# PRSC-2101-THCFS-1V3_eagle7.net
KiCad netlist of a schematic drawn in EAGLE
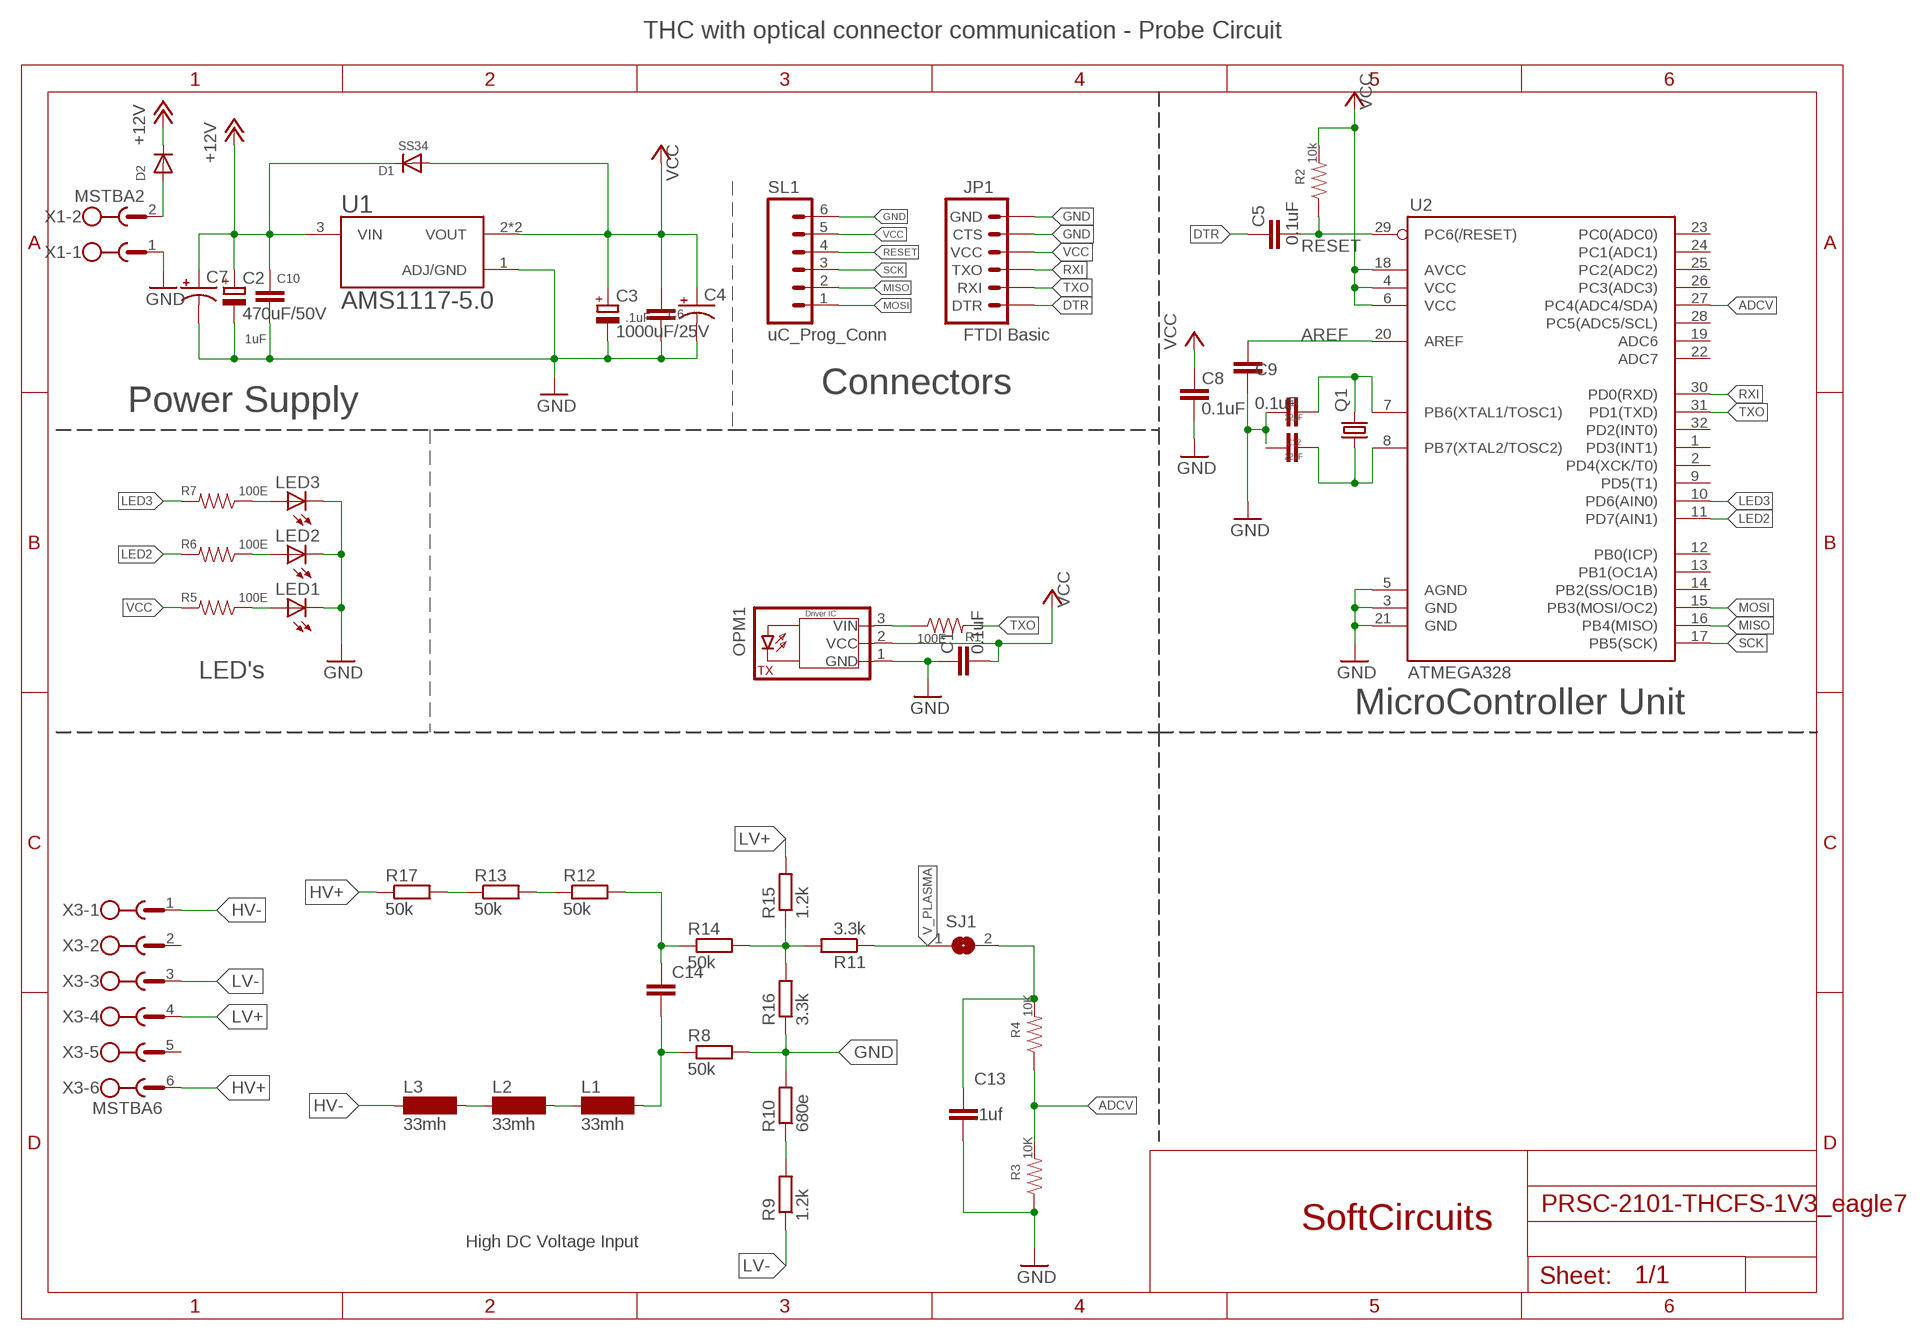
[diagram p0: schematic, sheet 1]

(export (version "E")
  (design (tool "Eeschema 10.0.6"))
  (components
    (comp (ref "C1")
      (value "0.1uF")
      (footprint "eagle-import:C1206")
      (libsource (lib "eagle-import") (part "C-EUC1206"))
    )
    (comp (ref "C2")
      (value "470uF/50V")
      (footprint "eagle-import:153CLV-1010")
      (libsource (lib "eagle-import") (part "CPOL-EU153CLV-1010"))
    )
    (comp (ref "C3")
      (value "1000uF/25V")
      (footprint "eagle-import:153CLV-1010")
      (libsource (lib "eagle-import") (part "CPOL-EU153CLV-1010"))
    )
    (comp (ref "C4")
      (value "CAP_POL3528-KIT")
      (footprint "eagle-import:EIA3528-KIT")
      (libsource (lib "eagle-import") (part "CAP_POL3528-KIT"))
    )
    (comp (ref "C5")
      (value "0.1uF")
      (footprint "eagle-import:C1206")
      (libsource (lib "eagle-import") (part "C-EUC1206"))
    )
    (comp (ref "C6")
      (value ".1uF")
      (footprint "eagle-import:C1206")
      (libsource (lib "eagle-import") (part "C-EUC1206"))
    )
    (comp (ref "C7")
      (value "CAP_POL3528-KIT")
      (footprint "eagle-import:EIA3528-KIT")
      (libsource (lib "eagle-import") (part "CAP_POL3528-KIT"))
    )
    (comp (ref "C8")
      (value "0.1uF")
      (footprint "eagle-import:C1206")
      (libsource (lib "eagle-import") (part "C-EUC1206"))
    )
    (comp (ref "C9")
      (value "0.1uF")
      (footprint "eagle-import:C1206")
      (libsource (lib "eagle-import") (part "C-EUC1206"))
    )
    (comp (ref "C10")
      (value "1uF")
      (footprint "eagle-import:C1206")
      (libsource (lib "eagle-import") (part "C-EUC1206"))
    )
    (comp (ref "C11")
      (value "22pF")
      (footprint "eagle-import:C1206")
      (libsource (lib "eagle-import") (part "C-EUC1206"))
    )
    (comp (ref "C12")
      (value "22pF")
      (footprint "eagle-import:C1206")
      (libsource (lib "eagle-import") (part "C-EUC1206"))
    )
    (comp (ref "C13")
      (value ".1uf")
      (footprint "eagle-import:C1206")
      (libsource (lib "eagle-import") (part "C-EUC1206"))
    )
    (comp (ref "C14")
      (value "C-EU050-025X075")
      (footprint "eagle-import:C050-025X075")
      (libsource (lib "eagle-import") (part "rcl_C-EU050-025X075"))
    )
    (comp (ref "D1")
      (value "SS34")
      (footprint "eagle-import:SMADIODE")
      (libsource (lib "eagle-import") (part "DIODESMA"))
    )
    (comp (ref "D2")
      (value "DIODESMA")
      (footprint "eagle-import:SMADIODE")
      (libsource (lib "eagle-import") (part "DIODESMA"))
    )
    (comp (ref "JP1")
      (value "FTDI Basic")
      (footprint "eagle-import:1X06")
      (libsource (lib "eagle-import") (part "ARDUINO_SERIAL_PROGRAMPTH"))
    )
    (comp (ref "L1")
      (value "33mh")
      (footprint "eagle-import:MY_INDUCTOR")
      (libsource (lib "eagle-import") (part "SD12"))
    )
    (comp (ref "L2")
      (value "33mh")
      (footprint "eagle-import:MY_INDUCTOR")
      (libsource (lib "eagle-import") (part "SD12"))
    )
    (comp (ref "L3")
      (value "33mh")
      (footprint "eagle-import:MY_INDUCTOR")
      (libsource (lib "eagle-import") (part "SD12"))
    )
    (comp (ref "LED1")
      (value "LED3MM")
      (footprint "eagle-import:LED3MM")
      (libsource (lib "eagle-import") (part "LED3MM"))
    )
    (comp (ref "LED2")
      (value "LED3MM")
      (footprint "eagle-import:LED3MM")
      (libsource (lib "eagle-import") (part "LED3MM"))
    )
    (comp (ref "LED3")
      (value "LED3MM")
      (footprint "eagle-import:LED3MM")
      (libsource (lib "eagle-import") (part "LED3MM"))
    )
    (comp (ref "OPM1")
      (value "TOSLINK_DQT-025")
      (footprint "eagle-import:TOSLINK_DQ-025")
      (libsource (lib "eagle-import") (part "TOSLINK_DQT-025"))
    )
    (comp (ref "Q1")
      (value "CRYSTALHC49UP")
      (footprint "eagle-import:HC49UP")
      (libsource (lib "eagle-import") (part "CRYSTALHC49UP"))
    )
    (comp (ref "R1")
      (value "100E")
      (footprint "eagle-import:1206")
      (libsource (lib "eagle-import") (part "RESISTOR1206"))
    )
    (comp (ref "R2")
      (value "10k")
      (footprint "eagle-import:1206")
      (libsource (lib "eagle-import") (part "RESISTOR1206"))
    )
    (comp (ref "R3")
      (value "10K")
      (footprint "eagle-import:1206")
      (libsource (lib "eagle-import") (part "RESISTOR1206"))
    )
    (comp (ref "R4")
      (value "10K")
      (footprint "eagle-import:1206")
      (libsource (lib "eagle-import") (part "RESISTOR1206"))
    )
    (comp (ref "R5")
      (value "100E")
      (footprint "eagle-import:1206")
      (libsource (lib "eagle-import") (part "RESISTOR1206"))
    )
    (comp (ref "R6")
      (value "100E")
      (footprint "eagle-import:1206")
      (libsource (lib "eagle-import") (part "RESISTOR1206"))
    )
    (comp (ref "R7")
      (value "100E")
      (footprint "eagle-import:1206")
      (libsource (lib "eagle-import") (part "RESISTOR1206"))
    )
    (comp (ref "R8")
      (value "50k")
      (footprint "eagle-import:0207_5V")
      (libsource (lib "eagle-import") (part "R-EU_0207/5V"))
    )
    (comp (ref "R9")
      (value "1.2k")
      (footprint "eagle-import:0207_2V")
      (libsource (lib "eagle-import") (part "R-EU_0207/2V"))
    )
    (comp (ref "R10")
      (value "680e")
      (footprint "eagle-import:0207_5V")
      (libsource (lib "eagle-import") (part "R-EU_0207/5V"))
    )
    (comp (ref "R11")
      (value "3.3k")
      (footprint "eagle-import:0207_2V")
      (libsource (lib "eagle-import") (part "R-EU_0207/2V"))
    )
    (comp (ref "R12")
      (value "50k")
      (footprint "eagle-import:0207_5V")
      (libsource (lib "eagle-import") (part "R-EU_0207/5V"))
    )
    (comp (ref "R13")
      (value "50k")
      (footprint "eagle-import:0207_5V")
      (libsource (lib "eagle-import") (part "R-EU_0207/5V"))
    )
    (comp (ref "R14")
      (value "50k")
      (footprint "eagle-import:0207_5V")
      (libsource (lib "eagle-import") (part "R-EU_0207/5V"))
    )
    (comp (ref "R15")
      (value "1.2k")
      (footprint "eagle-import:0207_2V")
      (libsource (lib "eagle-import") (part "R-EU_0207/2V"))
    )
    (comp (ref "R16")
      (value "3.3k")
      (footprint "eagle-import:0207_15")
      (libsource (lib "eagle-import") (part "R-EU_0207/15"))
    )
    (comp (ref "R17")
      (value "50k")
      (footprint "eagle-import:0207_5V")
      (libsource (lib "eagle-import") (part "R-EU_0207/5V"))
    )
    (comp (ref "SJ1") (value "SJ") (footprint "eagle-import:SJ") (libsource (lib "eagle-import") (part "SJ")))
    (comp (ref "SL1")
      (value "uC_Prog_Conn")
      (footprint "eagle-import:06P")
      (libsource (lib "eagle-import") (part "M06"))
    )
    (comp (ref "U1")
      (value "AMS1117-5.0")
      (footprint "eagle-import:SOT229P700X180-4N")
      (fields (field (name "MF") "Advanced Monolithic Systems"))
      (libsource (lib "eagle-import") (part "AMS1117-5.0"))
    )
    (comp (ref "U2")
      (value "ATMEGA328")
      (footprint "eagle-import:TQFP32-08")
      (libsource (lib "eagle-import") (part "ATMEGA168"))
    )
    (comp (ref "X1")
      (value "MSTBA2")
      (footprint "eagle-import:MSTBA2")
      (fields (field (name "MF") "FARNELL") (field (name "MPN") "1757242"))
      (libsource (lib "eagle-import") (part "MSTBA2"))
    )
    (comp (ref "X3")
      (value "MSTBA6")
      (footprint "eagle-import:MSTBA6")
      (fields (field (name "MF") "FARNELL") (field (name "MPN") "1757284"))
      (libsource (lib "eagle-import") (part "MSTBA6"))
    )
  )
  (nets
    (net (code "1") (name "+12V") (class "Default")
      (node (ref "C10") (pin "1") (pinfunction "1_1") (pintype "passive"))
      (node (ref "C2") (pin "+") (pinfunction "+_+") (pintype "passive"))
      (node (ref "C7") (pin "A") (pinfunction "+_A") (pintype "passive"))
      (node (ref "D1") (pin "C") (pinfunction "C_C") (pintype "passive"))
      (node (ref "D2") (pin "C") (pinfunction "C_C") (pintype "passive"))
      (node (ref "U1") (pin "3") (pinfunction "VIN_3") (pintype "input"))
    )
    (net (code "2") (name "/AREF") (class "Default")
      (node (ref "C9") (pin "2") (pinfunction "2_2") (pintype "passive"))
      (node (ref "U2") (pin "20") (pinfunction "AREF_20") (pintype "bidirectional"))
    )
    (net (code "3") (name "ADCV") (class "Default")
      (node (ref "R3") (pin "2") (pinfunction "2_2") (pintype "passive"))
      (node (ref "R4") (pin "1") (pinfunction "1_1") (pintype "passive"))
      (node (ref "U2") (pin "27") (pinfunction "PC4(ADC4/SDA)_27") (pintype "bidirectional"))
    )
    (net (code "4") (name "DTR") (class "Default")
      (node (ref "C5") (pin "2") (pinfunction "2_2") (pintype "passive"))
      (node (ref "JP1") (pin "1") (pinfunction "DTR_1") (pintype "passive"))
    )
    (net (code "5") (name "GND") (class "Default")
      (node (ref "C1") (pin "2") (pinfunction "2_2") (pintype "passive"))
      (node (ref "C10") (pin "2") (pinfunction "2_2") (pintype "passive"))
      (node (ref "C11") (pin "2") (pinfunction "2_2") (pintype "passive"))
      (node (ref "C12") (pin "2") (pinfunction "2_2") (pintype "passive"))
      (node (ref "C13") (pin "2") (pinfunction "2_2") (pintype "passive"))
      (node (ref "C2") (pin "-") (pinfunction "-_-") (pintype "passive"))
      (node (ref "C3") (pin "-") (pinfunction "-_-") (pintype "passive"))
      (node (ref "C4") (pin "C") (pinfunction "-_C") (pintype "passive"))
      (node (ref "C6") (pin "2") (pinfunction "2_2") (pintype "passive"))
      (node (ref "C7") (pin "C") (pinfunction "-_C") (pintype "passive"))
      (node (ref "C8") (pin "1") (pinfunction "1_1") (pintype "passive"))
      (node (ref "C9") (pin "1") (pinfunction "1_1") (pintype "passive"))
      (node (ref "JP1") (pin "5") (pinfunction "CTS_5") (pintype "passive"))
      (node (ref "JP1") (pin "6") (pinfunction "GND_6") (pintype "passive"))
      (node (ref "LED1") (pin "K") (pinfunction "C_K") (pintype "passive"))
      (node (ref "LED2") (pin "K") (pinfunction "C_K") (pintype "passive"))
      (node (ref "LED3") (pin "K") (pinfunction "C_K") (pintype "passive"))
      (node (ref "OPM1") (pin "1") (pinfunction "GND_1") (pintype "passive"))
      (node (ref "R10") (pin "2") (pinfunction "2_2") (pintype "passive"))
      (node (ref "R16") (pin "1") (pinfunction "1_1") (pintype "passive"))
      (node (ref "R3") (pin "1") (pinfunction "1_1") (pintype "passive"))
      (node (ref "R8") (pin "2") (pinfunction "2_2") (pintype "passive"))
      (node (ref "SL1") (pin "6") (pinfunction "6_6") (pintype "passive"))
      (node (ref "U1") (pin "1") (pinfunction "ADJ/GND_1") (pintype "power_in"))
      (node (ref "U2") (pin "21") (pinfunction "GND_21") (pintype "bidirectional"))
      (node (ref "U2") (pin "3") (pinfunction "GND_3") (pintype "bidirectional"))
      (node (ref "U2") (pin "5") (pinfunction "AGND_5") (pintype "bidirectional"))
      (node (ref "X1") (pin "1") (pinfunction "1_1") (pintype "passive"))
    )
    (net (code "6") (name "HV+") (class "Default")
      (node (ref "R17") (pin "1") (pinfunction "1_1") (pintype "passive"))
      (node (ref "X3") (pin "6") (pinfunction "1_6") (pintype "passive"))
    )
    (net (code "7") (name "HV-") (class "Default")
      (node (ref "L3") (pin "1") (pinfunction "1_1") (pintype "passive"))
      (node (ref "X3") (pin "1") (pinfunction "1_1") (pintype "passive"))
    )
    (net (code "8") (name "LED2") (class "Default")
      (node (ref "R6") (pin "2") (pinfunction "2_2") (pintype "passive"))
      (node (ref "U2") (pin "11") (pinfunction "PD7(AIN1)_11") (pintype "bidirectional"))
    )
    (net (code "9") (name "LED3") (class "Default")
      (node (ref "R7") (pin "2") (pinfunction "2_2") (pintype "passive"))
      (node (ref "U2") (pin "10") (pinfunction "PD6(AIN0)_10") (pintype "bidirectional"))
    )
    (net (code "10") (name "LV+") (class "Default")
      (node (ref "R15") (pin "2") (pinfunction "2_2") (pintype "passive"))
      (node (ref "X3") (pin "4") (pinfunction "1_4") (pintype "passive"))
    )
    (net (code "11") (name "LV-") (class "Default")
      (node (ref "R9") (pin "1") (pinfunction "1_1") (pintype "passive"))
      (node (ref "X3") (pin "3") (pinfunction "1_3") (pintype "passive"))
    )
    (net (code "12") (name "MISO") (class "Default")
      (node (ref "SL1") (pin "2") (pinfunction "2_2") (pintype "passive"))
      (node (ref "U2") (pin "16") (pinfunction "PB4(MISO)_16") (pintype "bidirectional"))
    )
    (net (code "13") (name "MOSI") (class "Default")
      (node (ref "SL1") (pin "1") (pinfunction "1_1") (pintype "passive"))
      (node (ref "U2") (pin "15") (pinfunction "PB3(MOSI/OC2)_15") (pintype "bidirectional"))
    )
    (net (code "14") (name "Net-(C13-Pad1)") (class "Default")
      (node (ref "C13") (pin "1") (pinfunction "1_1") (pintype "passive"))
      (node (ref "R4") (pin "2") (pinfunction "2_2") (pintype "passive"))
      (node (ref "SJ1") (pin "2") (pinfunction "2_2") (pintype "passive"))
    )
    (net (code "15") (name "Net-(C14-Pad1)") (class "Default")
      (node (ref "C14") (pin "1") (pinfunction "1_1") (pintype "passive"))
      (node (ref "R12") (pin "2") (pinfunction "2_2") (pintype "passive"))
      (node (ref "R14") (pin "1") (pinfunction "1_1") (pintype "passive"))
    )
    (net (code "16") (name "Net-(C14-Pad2)") (class "Default")
      (node (ref "C14") (pin "2") (pinfunction "2_2") (pintype "passive"))
      (node (ref "L1") (pin "2") (pinfunction "2_2") (pintype "passive"))
      (node (ref "R8") (pin "1") (pinfunction "1_1") (pintype "passive"))
    )
    (net (code "17") (name "Net-(L1-Pad1)") (class "Default")
      (node (ref "L1") (pin "1") (pinfunction "1_1") (pintype "passive"))
      (node (ref "L2") (pin "2") (pinfunction "2_2") (pintype "passive"))
    )
    (net (code "18") (name "Net-(L2-Pad1)") (class "Default")
      (node (ref "L2") (pin "1") (pinfunction "1_1") (pintype "passive"))
      (node (ref "L3") (pin "2") (pinfunction "2_2") (pintype "passive"))
    )
    (net (code "19") (name "Net-(LED1-PadA)") (class "Default")
      (node (ref "LED1") (pin "A") (pinfunction "A_A") (pintype "passive"))
      (node (ref "R5") (pin "1") (pinfunction "1_1") (pintype "passive"))
    )
    (net (code "20") (name "Net-(LED2-PadA)") (class "Default")
      (node (ref "LED2") (pin "A") (pinfunction "A_A") (pintype "passive"))
      (node (ref "R6") (pin "1") (pinfunction "1_1") (pintype "passive"))
    )
    (net (code "21") (name "Net-(LED3-PadA)") (class "Default")
      (node (ref "LED3") (pin "A") (pinfunction "A_A") (pintype "passive"))
      (node (ref "R7") (pin "1") (pinfunction "1_1") (pintype "passive"))
    )
    (net (code "22") (name "Net-(OPM1-VIN)") (class "Default")
      (node (ref "OPM1") (pin "3") (pinfunction "VIN_3") (pintype "passive"))
      (node (ref "R1") (pin "1") (pinfunction "1_1") (pintype "passive"))
    )
    (net (code "23") (name "Net-(R10-Pad1)") (class "Default")
      (node (ref "R10") (pin "1") (pinfunction "1_1") (pintype "passive"))
      (node (ref "R9") (pin "2") (pinfunction "2_2") (pintype "passive"))
    )
    (net (code "24") (name "Net-(R11-Pad2)") (class "Default")
      (node (ref "R11") (pin "2") (pinfunction "2_2") (pintype "passive"))
      (node (ref "R14") (pin "2") (pinfunction "2_2") (pintype "passive"))
      (node (ref "R15") (pin "1") (pinfunction "1_1") (pintype "passive"))
      (node (ref "R16") (pin "2") (pinfunction "2_2") (pintype "passive"))
    )
    (net (code "25") (name "Net-(R12-Pad1)") (class "Default")
      (node (ref "R12") (pin "1") (pinfunction "1_1") (pintype "passive"))
      (node (ref "R13") (pin "2") (pinfunction "2_2") (pintype "passive"))
    )
    (net (code "26") (name "Net-(R13-Pad1)") (class "Default")
      (node (ref "R13") (pin "1") (pinfunction "1_1") (pintype "passive"))
      (node (ref "R17") (pin "2") (pinfunction "2_2") (pintype "passive"))
    )
    (net (code "27") (name "Net-(U2-PB6(XTAL1{slash}TOSC1))") (class "Default")
      (node (ref "C11") (pin "1") (pinfunction "1_1") (pintype "passive"))
      (node (ref "Q1") (pin "2") (pinfunction "2_2") (pintype "passive"))
      (node (ref "U2") (pin "7") (pinfunction "PB6(XTAL1/TOSC1)_7") (pintype "bidirectional"))
    )
    (net (code "28") (name "Net-(U2-PB7(XTAL2{slash}TOSC2))") (class "Default")
      (node (ref "C12") (pin "1") (pinfunction "1_1") (pintype "passive"))
      (node (ref "Q1") (pin "1") (pinfunction "1_1") (pintype "passive"))
      (node (ref "U2") (pin "8") (pinfunction "PB7(XTAL2/TOSC2)_8") (pintype "bidirectional"))
    )
    (net (code "29") (name "Net-(X1B-1)") (class "Default")
      (node (ref "D2") (pin "A") (pinfunction "A_A") (pintype "passive"))
      (node (ref "X1") (pin "2") (pinfunction "1_2") (pintype "passive"))
    )
    (net (code "30") (name "RESET") (class "Default")
      (node (ref "C5") (pin "1") (pinfunction "1_1") (pintype "passive"))
      (node (ref "R2") (pin "1") (pinfunction "1_1") (pintype "passive"))
      (node (ref "SL1") (pin "4") (pinfunction "4_4") (pintype "passive"))
      (node (ref "U2") (pin "29") (pinfunction "PC6(/RESET)_29") (pintype "bidirectional"))
    )
    (net (code "31") (name "RXI") (class "Default")
      (node (ref "JP1") (pin "3") (pinfunction "TXO_3") (pintype "passive"))
      (node (ref "U2") (pin "30") (pinfunction "PD0(RXD)_30") (pintype "bidirectional"))
    )
    (net (code "32") (name "SCK") (class "Default")
      (node (ref "SL1") (pin "3") (pinfunction "3_3") (pintype "passive"))
      (node (ref "U2") (pin "17") (pinfunction "PB5(SCK)_17") (pintype "bidirectional"))
    )
    (net (code "33") (name "TXO") (class "Default")
      (node (ref "JP1") (pin "2") (pinfunction "RXI_2") (pintype "passive"))
      (node (ref "R1") (pin "2") (pinfunction "2_2") (pintype "passive"))
      (node (ref "U2") (pin "31") (pinfunction "PD1(TXD)_31") (pintype "bidirectional"))
    )
    (net (code "34") (name "VCC") (class "Default")
      (node (ref "C1") (pin "1") (pinfunction "1_1") (pintype "passive"))
      (node (ref "C3") (pin "+") (pinfunction "+_+") (pintype "passive"))
      (node (ref "C4") (pin "A") (pinfunction "+_A") (pintype "passive"))
      (node (ref "C6") (pin "1") (pinfunction "1_1") (pintype "passive"))
      (node (ref "C8") (pin "2") (pinfunction "2_2") (pintype "passive"))
      (node (ref "D1") (pin "A") (pinfunction "A_A") (pintype "passive"))
      (node (ref "JP1") (pin "4") (pinfunction "VCC_4") (pintype "passive"))
      (node (ref "OPM1") (pin "2") (pinfunction "VCC_2") (pintype "bidirectional"))
      (node (ref "R2") (pin "2") (pinfunction "2_2") (pintype "passive"))
      (node (ref "R5") (pin "2") (pinfunction "2_2") (pintype "passive"))
      (node (ref "SL1") (pin "5") (pinfunction "5_5") (pintype "passive"))
      (node (ref "U1") (pin "2") (pinfunction "VOUT_2") (pintype "output"))
      (node (ref "U1") (pin "4") (pinfunction "VOUT_4") (pintype "output"))
      (node (ref "U2") (pin "18") (pinfunction "AVCC_18") (pintype "bidirectional"))
      (node (ref "U2") (pin "4") (pinfunction "VCC_4") (pintype "bidirectional"))
      (node (ref "U2") (pin "6") (pinfunction "VCC_6") (pintype "bidirectional"))
    )
    (net (code "35") (name "V_PLASMA") (class "Default")
      (node (ref "R11") (pin "1") (pinfunction "1_1") (pintype "passive"))
      (node (ref "SJ1") (pin "1") (pinfunction "1_1") (pintype "passive"))
    )
    (net (code "36") (name "unconnected-(U2-ADC6-Pad19)") (class "Default")
      (node (ref "U2") (pin "19") (pinfunction "ADC6_19") (pintype "bidirectional"))
    )
    (net (code "37") (name "unconnected-(U2-ADC7-Pad22)") (class "Default")
      (node (ref "U2") (pin "22") (pinfunction "ADC7_22") (pintype "bidirectional"))
    )
    (net (code "38") (name "unconnected-(U2-PB0(ICP)-Pad12)") (class "Default")
      (node (ref "U2") (pin "12") (pinfunction "PB0(ICP)_12") (pintype "bidirectional"))
    )
    (net (code "39") (name "unconnected-(U2-PB1(OC1A)-Pad13)") (class "Default")
      (node (ref "U2") (pin "13") (pinfunction "PB1(OC1A)_13") (pintype "bidirectional"))
    )
    (net (code "40") (name "unconnected-(U2-PB2(SS{slash}OC1B)-Pad14)") (class "Default")
      (node (ref "U2") (pin "14") (pinfunction "PB2(SS/OC1B)_14") (pintype "bidirectional"))
    )
    (net (code "41") (name "unconnected-(U2-PC0(ADC0)-Pad23)") (class "Default")
      (node (ref "U2") (pin "23") (pinfunction "PC0(ADC0)_23") (pintype "bidirectional"))
    )
    (net (code "42") (name "unconnected-(U2-PC1(ADC1)-Pad24)") (class "Default")
      (node (ref "U2") (pin "24") (pinfunction "PC1(ADC1)_24") (pintype "bidirectional"))
    )
    (net (code "43") (name "unconnected-(U2-PC2(ADC2)-Pad25)") (class "Default")
      (node (ref "U2") (pin "25") (pinfunction "PC2(ADC2)_25") (pintype "bidirectional"))
    )
    (net (code "44") (name "unconnected-(U2-PC3(ADC3)-Pad26)") (class "Default")
      (node (ref "U2") (pin "26") (pinfunction "PC3(ADC3)_26") (pintype "bidirectional"))
    )
    (net (code "45") (name "unconnected-(U2-PC5(ADC5{slash}SCL)-Pad28)") (class "Default")
      (node (ref "U2") (pin "28") (pinfunction "PC5(ADC5/SCL)_28") (pintype "bidirectional"))
    )
    (net (code "46") (name "unconnected-(U2-PD2(INT0)-Pad32)") (class "Default")
      (node (ref "U2") (pin "32") (pinfunction "PD2(INT0)_32") (pintype "bidirectional"))
    )
    (net (code "47") (name "unconnected-(U2-PD3(INT1)-Pad1)") (class "Default")
      (node (ref "U2") (pin "1") (pinfunction "PD3(INT1)_1") (pintype "bidirectional"))
    )
    (net (code "48") (name "unconnected-(U2-PD4(XCK{slash}T0)-Pad2)") (class "Default")
      (node (ref "U2") (pin "2") (pinfunction "PD4(XCK/T0)_2") (pintype "bidirectional"))
    )
    (net (code "49") (name "unconnected-(U2-PD5(T1)-Pad9)") (class "Default")
      (node (ref "U2") (pin "9") (pinfunction "PD5(T1)_9") (pintype "bidirectional"))
    )
    (net (code "50") (name "unconnected-(X3B-1-Pad2)") (class "Default")
      (node (ref "X3") (pin "2") (pinfunction "1_2") (pintype "passive"))
    )
    (net (code "51") (name "unconnected-(X3E-1-Pad5)") (class "Default")
      (node (ref "X3") (pin "5") (pinfunction "1_5") (pintype "passive"))
    )
  )
)
